# mathFunTest.net
KiCad netlist of a schematic drawn in Altium Designer
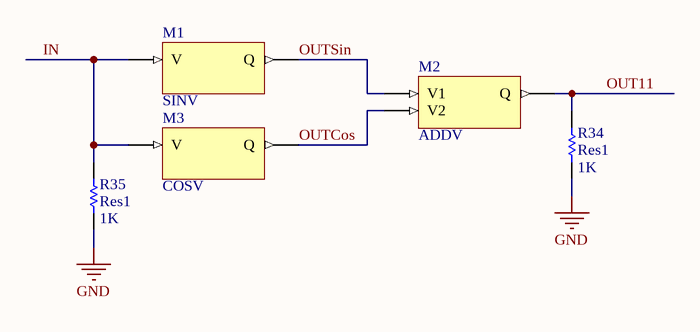
[diagram p0: mathFunTest.SchDoc]

(export (version "E")
  (design (tool "Eeschema 10.0.6"))
  (components
    (comp (ref "M1")
      (value "SINV")
      (description "Sine of Voltage")
      (fields (field (name "PUBLISHER") "Altium Limited"))
      (libsource (lib "Simulation Math Function") (part "SINV"))
    )
    (comp (ref "M2")
      (value "ADDV")
      (description "Add Voltages")
      (fields (field (name "PUBLISHER") "Altium Limited"))
      (libsource (lib "Simulation Math Function") (part "ADDV"))
    )
    (comp (ref "M3")
      (value "COSV")
      (description "Cosine of Voltage")
      (fields (field (name "PUBLISHER") "Altium Limited"))
      (libsource (lib "Simulation Math Function") (part "COSV"))
    )
    (comp (ref "R34")
      (value "Res1")
      (footprint "AXIAL-0.3")
      (description "Resistor")
      (fields (field (name "ALTIUM_VALUE") "1K") (field (name "PUBLISHER") "Altium Limited"))
      (libsource (lib "Miscellaneous Devices") (part "Res1"))
    )
    (comp (ref "R35")
      (value "Res1")
      (footprint "AXIAL-0.3")
      (description "Resistor")
      (fields (field (name "ALTIUM_VALUE") "1K") (field (name "PUBLISHER") "Altium Limited"))
      (libsource (lib "Miscellaneous Devices") (part "Res1"))
    )
  )
  (nets
    (net (code "1") (name "/IN") (class "Default")
      (node (ref "M1") (pin "1") (pinfunction "V_1") (pintype "input"))
      (node (ref "M3") (pin "1") (pinfunction "V_1") (pintype "input"))
      (node (ref "R35") (pin "1") (pinfunction "1_1") (pintype "passive"))
    )
    (net (code "2") (name "/OUT11") (class "Default")
      (node (ref "M2") (pin "3") (pinfunction "Q_3") (pintype "output"))
      (node (ref "R34") (pin "1") (pinfunction "1_1") (pintype "passive"))
    )
    (net (code "3") (name "/OUTCos") (class "Default")
      (node (ref "M2") (pin "2") (pinfunction "V2_2") (pintype "input"))
      (node (ref "M3") (pin "2") (pinfunction "Q_2") (pintype "output"))
    )
    (net (code "4") (name "/OUTSin") (class "Default")
      (node (ref "M1") (pin "2") (pinfunction "Q_2") (pintype "output"))
      (node (ref "M2") (pin "1") (pinfunction "V1_1") (pintype "input"))
    )
    (net (code "5") (name "GND") (class "Default")
      (node (ref "R34") (pin "2") (pinfunction "2_2") (pintype "passive"))
      (node (ref "R35") (pin "2") (pinfunction "2_2") (pintype "passive"))
    )
  )
)
